# Switching_Circuits.net
KiCad netlist of a schematic drawn in Altium Designer
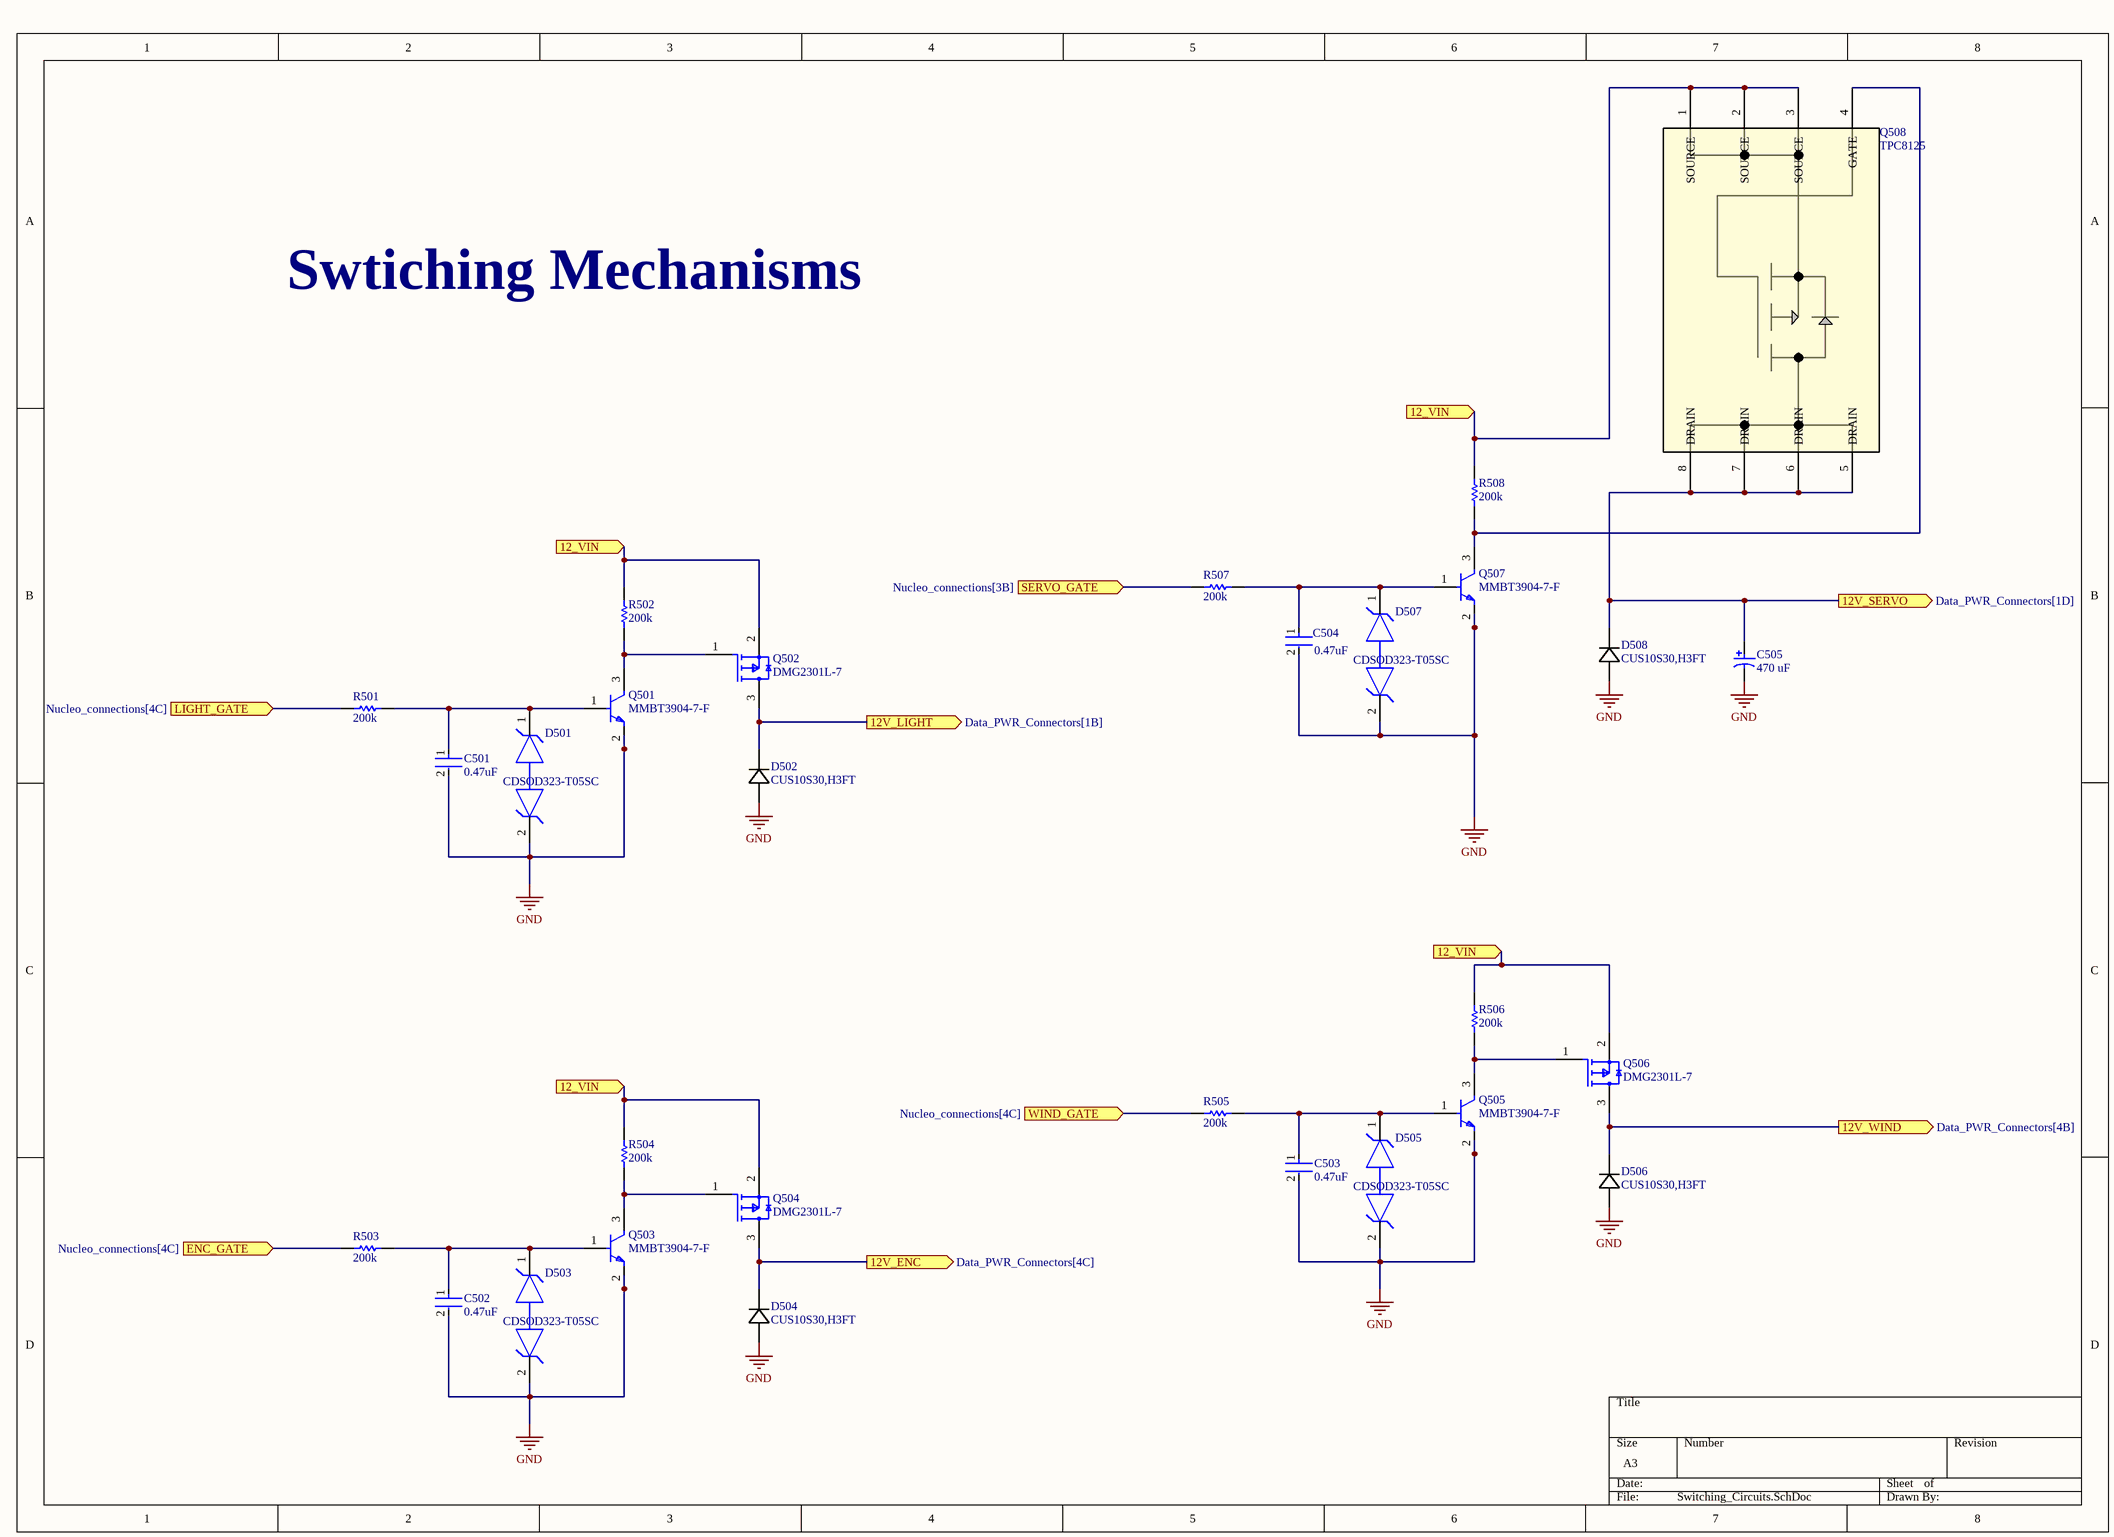
[diagram p0: Switching_Circuits.SchDoc]

(export (version "E")
  (design (tool "Eeschema 10.0.6"))
  (components
    (comp (ref "C501")
      (value "0.47uF")
      (footprint "FP-GRM21B-0_15-IPC_B")
      (description "Chip Multilayer Ceramic Capacitors for General Purpose, 0805, 0.47uF, X7R, 15%, 10%, 100V")
      (fields (field (name "VOLTAGE") "100V") (field (name "TOLERANCE") "10%"))
      (libsource (lib "Altium Content Vault") (part "b4654b650e69147ec39a6b967a45e02"))
    )
    (comp (ref "C502")
      (value "0.47uF")
      (footprint "FP-GRM21B-0_15-IPC_B")
      (description "Chip Multilayer Ceramic Capacitors for General Purpose, 0805, 0.47uF, X7R, 15%, 10%, 100V")
      (fields (field (name "VOLTAGE") "100V") (field (name "TOLERANCE") "10%"))
      (libsource (lib "Altium Content Vault") (part "b4654b650e69147ec39a6b967a45e02"))
    )
    (comp (ref "C503")
      (value "0.47uF")
      (footprint "FP-GRM21B-0_15-IPC_B")
      (description "Chip Multilayer Ceramic Capacitors for General Purpose, 0805, 0.47uF, X7R, 15%, 10%, 100V")
      (fields (field (name "VOLTAGE") "100V") (field (name "TOLERANCE") "10%"))
      (libsource (lib "Altium Content Vault") (part "b4654b650e69147ec39a6b967a45e02"))
    )
    (comp (ref "C504")
      (value "0.47uF")
      (footprint "FP-GRM21B-0_15-IPC_B")
      (description "Chip Multilayer Ceramic Capacitors for General Purpose, 0805, 0.47uF, X7R, 15%, 10%, 100V")
      (fields (field (name "VOLTAGE") "100V") (field (name "TOLERANCE") "10%"))
      (libsource (lib "Altium Content Vault") (part "b4654b650e69147ec39a6b967a45e02"))
    )
    (comp (ref "C505")
      (value "470 uF")
      (footprint "PNSC-CAP-10x20-P2")
      (description "Aluminum Electrolytic Capacitor, 470 uF, +/- 20%, 50 V, -55 to 105 degC, 2-Pin THD, RoHS, Bulk")
      (fields (field (name "MANUFACTURER") "Panasonic"))
      (libsource (lib "Altium Content Vault") (part "CAP-P-2"))
    )
    (comp (ref "D501")
      (value "CDSOD323-T05SC")
      (footprint "FP-SOD-323-CA-MFG")
      (description "TVS DIODE 5VWM 14.5VC SOD323")
      (libsource (lib "Altium Content Vault") (part "c43c1b0add0eb72e36bdc657e82fc73"))
    )
    (comp (ref "D502")
      (value "CUS10S30,H3FT")
      (footprint "USC_TOS")
      (description "No Description Available")
      (libsource (lib "Schlib1") (part "CUS10S30,H3FT"))
    )
    (comp (ref "D503")
      (value "CDSOD323-T05SC")
      (footprint "FP-SOD-323-CA-MFG")
      (description "TVS DIODE 5VWM 14.5VC SOD323")
      (libsource (lib "Altium Content Vault") (part "c43c1b0add0eb72e36bdc657e82fc73"))
    )
    (comp (ref "D504")
      (value "CUS10S30,H3FT")
      (footprint "USC_TOS")
      (description "No Description Available")
      (libsource (lib "Schlib1") (part "CUS10S30,H3FT"))
    )
    (comp (ref "D505")
      (value "CDSOD323-T05SC")
      (footprint "FP-SOD-323-CA-MFG")
      (description "TVS DIODE 5VWM 14.5VC SOD323")
      (libsource (lib "Altium Content Vault") (part "c43c1b0add0eb72e36bdc657e82fc73"))
    )
    (comp (ref "D506")
      (value "CUS10S30,H3FT")
      (footprint "USC_TOS")
      (description "No Description Available")
      (libsource (lib "Schlib1") (part "CUS10S30,H3FT"))
    )
    (comp (ref "D507")
      (value "CDSOD323-T05SC")
      (footprint "FP-SOD-323-CA-MFG")
      (description "TVS DIODE 5VWM 14.5VC SOD323")
      (libsource (lib "Altium Content Vault") (part "c43c1b0add0eb72e36bdc657e82fc73"))
    )
    (comp (ref "D508")
      (value "CUS10S30,H3FT")
      (footprint "USC_TOS")
      (description "No Description Available")
      (libsource (lib "Schlib1") (part "CUS10S30,H3FT"))
    )
    (comp (ref "Q501")
      (value "MMBT3904-7-F")
      (footprint "FP-SOT23-IPC_A")
      (description "TRANS NPN 40V 0.2A SMD SOT23-3")
      (libsource (lib "Altium Content Vault") (part "b44e953556f554d0102664c7d152cb4"))
    )
    (comp (ref "Q502")
      (value "DMG2301L-7")
      (footprint "FP-SOT23-MFG")
      (description "MOSFET P-CH 20V 3A SOT23")
      (fields
        (field (name "MANUFACTURER") "Diodes Inc.")
        (field (name "OCTOPART") "https://octopart.com/dmg2301l-7-diodes+inc.-67250456")
      )
      (libsource (lib "Altium Content Vault") (part "b8f99f9e586195791e7fb11725ebaeb"))
    )
    (comp (ref "Q503")
      (value "MMBT3904-7-F")
      (footprint "FP-SOT23-IPC_A")
      (description "TRANS NPN 40V 0.2A SMD SOT23-3")
      (libsource (lib "Altium Content Vault") (part "b44e953556f554d0102664c7d152cb4"))
    )
    (comp (ref "Q504")
      (value "DMG2301L-7")
      (footprint "FP-SOT23-MFG")
      (description "MOSFET P-CH 20V 3A SOT23")
      (fields
        (field (name "MANUFACTURER") "Diodes Inc.")
        (field (name "OCTOPART") "https://octopart.com/dmg2301l-7-diodes+inc.-67250456")
      )
      (libsource (lib "Altium Content Vault") (part "b8f99f9e586195791e7fb11725ebaeb"))
    )
    (comp (ref "Q505")
      (value "MMBT3904-7-F")
      (footprint "FP-SOT23-IPC_A")
      (description "TRANS NPN 40V 0.2A SMD SOT23-3")
      (libsource (lib "Altium Content Vault") (part "b44e953556f554d0102664c7d152cb4"))
    )
    (comp (ref "Q506")
      (value "DMG2301L-7")
      (footprint "FP-SOT23-MFG")
      (description "MOSFET P-CH 20V 3A SOT23")
      (fields
        (field (name "MANUFACTURER") "Diodes Inc.")
        (field (name "OCTOPART") "https://octopart.com/dmg2301l-7-diodes+inc.-67250456")
      )
      (libsource (lib "Altium Content Vault") (part "b8f99f9e586195791e7fb11725ebaeb"))
    )
    (comp (ref "Q507")
      (value "MMBT3904-7-F")
      (footprint "FP-SOT23-IPC_A")
      (description "TRANS NPN 40V 0.2A SMD SOT23-3")
      (libsource (lib "Altium Content Vault") (part "b44e953556f554d0102664c7d152cb4"))
    )
    (comp (ref "Q508")
      (value "TPC8125")
      (footprint "SOP-8_TOS")
      (description "No Description Available")
      (libsource (lib "Schlib1") (part "TPC8125"))
    )
    (comp (ref "R501")
      (value "200k")
      (footprint "RESC2013X70X40LL20T20")
      (fields (field (name "MANUFACTURER") "Panasonic") (field (name "PART NUMBER") "ERJ-6ENF2003V"))
      (libsource (lib "Altium Content Vault") (part "RES"))
    )
    (comp (ref "R502")
      (value "200k")
      (footprint "RESC2013X70X40LL20T20")
      (fields (field (name "MANUFACTURER") "Panasonic") (field (name "PART NUMBER") "ERJ-6ENF2003V"))
      (libsource (lib "Altium Content Vault") (part "RES"))
    )
    (comp (ref "R503")
      (value "200k")
      (footprint "RESC2013X70X40LL20T20")
      (fields (field (name "MANUFACTURER") "Panasonic") (field (name "PART NUMBER") "ERJ-6ENF2003V"))
      (libsource (lib "Altium Content Vault") (part "RES"))
    )
    (comp (ref "R504")
      (value "200k")
      (footprint "RESC2013X70X40LL20T20")
      (fields (field (name "MANUFACTURER") "Panasonic") (field (name "PART NUMBER") "ERJ-6ENF2003V"))
      (libsource (lib "Altium Content Vault") (part "RES"))
    )
    (comp (ref "R505")
      (value "200k")
      (footprint "RESC2013X70X40LL20T20")
      (fields (field (name "MANUFACTURER") "Panasonic") (field (name "PART NUMBER") "ERJ-6ENF2003V"))
      (libsource (lib "Altium Content Vault") (part "RES"))
    )
    (comp (ref "R506")
      (value "200k")
      (footprint "RESC2013X70X40LL20T20")
      (fields (field (name "MANUFACTURER") "Panasonic") (field (name "PART NUMBER") "ERJ-6ENF2003V"))
      (libsource (lib "Altium Content Vault") (part "RES"))
    )
    (comp (ref "R507")
      (value "200k")
      (footprint "RESC2013X70X40LL20T20")
      (fields (field (name "MANUFACTURER") "Panasonic") (field (name "PART NUMBER") "ERJ-6ENF2003V"))
      (libsource (lib "Altium Content Vault") (part "RES"))
    )
    (comp (ref "R508")
      (value "200k")
      (footprint "RESC2013X70X40LL20T20")
      (fields (field (name "MANUFACTURER") "Panasonic") (field (name "PART NUMBER") "ERJ-6ENF2003V"))
      (libsource (lib "Altium Content Vault") (part "RES"))
    )
  )
  (nets
    (net (code "1") (name "/12V_ENC") (class "Default")
      (node (ref "D504") (pin "1") (pinfunction "cathode_1") (pintype "passive"))
      (node (ref "Q504") (pin "3") (pinfunction "D_3") (pintype "passive"))
    )
    (net (code "2") (name "/12V_LIGHT") (class "Default")
      (node (ref "D502") (pin "1") (pinfunction "cathode_1") (pintype "passive"))
      (node (ref "Q502") (pin "3") (pinfunction "D_3") (pintype "passive"))
    )
    (net (code "3") (name "/12V_SERVO") (class "Default")
      (node (ref "C505") (pin "1") (pinfunction "1_1") (pintype "passive"))
      (node (ref "D508") (pin "1") (pinfunction "cathode_1") (pintype "passive"))
      (node (ref "Q508") (pin "5") (pinfunction "DRAIN_5") (pintype "passive"))
      (node (ref "Q508") (pin "6") (pinfunction "DRAIN_6") (pintype "passive"))
      (node (ref "Q508") (pin "7") (pinfunction "DRAIN_7") (pintype "passive"))
      (node (ref "Q508") (pin "8") (pinfunction "DRAIN_8") (pintype "passive"))
    )
    (net (code "4") (name "/12V_WIND") (class "Default")
      (node (ref "D506") (pin "1") (pinfunction "cathode_1") (pintype "passive"))
      (node (ref "Q506") (pin "3") (pinfunction "D_3") (pintype "passive"))
    )
    (net (code "5") (name "/12_VIN") (class "Default")
      (node (ref "Q502") (pin "2") (pinfunction "S_2") (pintype "passive"))
      (node (ref "Q504") (pin "2") (pinfunction "S_2") (pintype "passive"))
      (node (ref "Q506") (pin "2") (pinfunction "S_2") (pintype "passive"))
      (node (ref "Q508") (pin "1") (pinfunction "SOURCE_1") (pintype "passive"))
      (node (ref "Q508") (pin "2") (pinfunction "SOURCE_2") (pintype "passive"))
      (node (ref "Q508") (pin "3") (pinfunction "SOURCE_3") (pintype "passive"))
      (node (ref "R502") (pin "2") (pinfunction "2_2") (pintype "passive"))
      (node (ref "R504") (pin "2") (pinfunction "2_2") (pintype "passive"))
      (node (ref "R506") (pin "2") (pinfunction "2_2") (pintype "passive"))
      (node (ref "R508") (pin "2") (pinfunction "2_2") (pintype "passive"))
    )
    (net (code "6") (name "/ENC_GATE") (class "Default")
      (node (ref "R503") (pin "1") (pinfunction "1_1") (pintype "passive"))
    )
    (net (code "7") (name "/LIGHT_GATE") (class "Default")
      (node (ref "R501") (pin "1") (pinfunction "1_1") (pintype "passive"))
    )
    (net (code "8") (name "/SERVO_GATE") (class "Default")
      (node (ref "R507") (pin "1") (pinfunction "1_1") (pintype "passive"))
    )
    (net (code "9") (name "/WIND_GATE") (class "Default")
      (node (ref "R505") (pin "1") (pinfunction "1_1") (pintype "passive"))
    )
    (net (code "10") (name "GND") (class "Default")
      (node (ref "C501") (pin "2") (pinfunction "2_2") (pintype "passive"))
      (node (ref "C502") (pin "2") (pinfunction "2_2") (pintype "passive"))
      (node (ref "C503") (pin "2") (pinfunction "2_2") (pintype "passive"))
      (node (ref "C504") (pin "2") (pinfunction "2_2") (pintype "passive"))
      (node (ref "C505") (pin "2") (pinfunction "2_2") (pintype "passive"))
      (node (ref "D501") (pin "2") (pinfunction "2_2") (pintype "passive"))
      (node (ref "D502") (pin "2") (pinfunction "anode_2") (pintype "passive"))
      (node (ref "D503") (pin "2") (pinfunction "2_2") (pintype "passive"))
      (node (ref "D504") (pin "2") (pinfunction "anode_2") (pintype "passive"))
      (node (ref "D505") (pin "2") (pinfunction "2_2") (pintype "passive"))
      (node (ref "D506") (pin "2") (pinfunction "anode_2") (pintype "passive"))
      (node (ref "D507") (pin "2") (pinfunction "2_2") (pintype "passive"))
      (node (ref "D508") (pin "2") (pinfunction "anode_2") (pintype "passive"))
      (node (ref "Q501") (pin "2") (pinfunction "E_2") (pintype "passive"))
      (node (ref "Q503") (pin "2") (pinfunction "E_2") (pintype "passive"))
      (node (ref "Q505") (pin "2") (pinfunction "E_2") (pintype "passive"))
      (node (ref "Q507") (pin "2") (pinfunction "E_2") (pintype "passive"))
    )
    (net (code "11") (name "Net-(Q501-B)") (class "Default")
      (node (ref "C501") (pin "1") (pinfunction "1_1") (pintype "passive"))
      (node (ref "D501") (pin "1") (pinfunction "1_1") (pintype "passive"))
      (node (ref "Q501") (pin "1") (pinfunction "B_1") (pintype "passive"))
      (node (ref "R501") (pin "2") (pinfunction "2_2") (pintype "passive"))
    )
    (net (code "12") (name "Net-(Q501-C)") (class "Default")
      (node (ref "Q501") (pin "3") (pinfunction "C_3") (pintype "passive"))
      (node (ref "Q502") (pin "1") (pinfunction "G_1") (pintype "passive"))
      (node (ref "R502") (pin "1") (pinfunction "1_1") (pintype "passive"))
    )
    (net (code "13") (name "Net-(Q503-B)") (class "Default")
      (node (ref "C502") (pin "1") (pinfunction "1_1") (pintype "passive"))
      (node (ref "D503") (pin "1") (pinfunction "1_1") (pintype "passive"))
      (node (ref "Q503") (pin "1") (pinfunction "B_1") (pintype "passive"))
      (node (ref "R503") (pin "2") (pinfunction "2_2") (pintype "passive"))
    )
    (net (code "14") (name "Net-(Q503-C)") (class "Default")
      (node (ref "Q503") (pin "3") (pinfunction "C_3") (pintype "passive"))
      (node (ref "Q504") (pin "1") (pinfunction "G_1") (pintype "passive"))
      (node (ref "R504") (pin "1") (pinfunction "1_1") (pintype "passive"))
    )
    (net (code "15") (name "Net-(Q505-B)") (class "Default")
      (node (ref "C503") (pin "1") (pinfunction "1_1") (pintype "passive"))
      (node (ref "D505") (pin "1") (pinfunction "1_1") (pintype "passive"))
      (node (ref "Q505") (pin "1") (pinfunction "B_1") (pintype "passive"))
      (node (ref "R505") (pin "2") (pinfunction "2_2") (pintype "passive"))
    )
    (net (code "16") (name "Net-(Q505-C)") (class "Default")
      (node (ref "Q505") (pin "3") (pinfunction "C_3") (pintype "passive"))
      (node (ref "Q506") (pin "1") (pinfunction "G_1") (pintype "passive"))
      (node (ref "R506") (pin "1") (pinfunction "1_1") (pintype "passive"))
    )
    (net (code "17") (name "Net-(Q507-B)") (class "Default")
      (node (ref "C504") (pin "1") (pinfunction "1_1") (pintype "passive"))
      (node (ref "D507") (pin "1") (pinfunction "1_1") (pintype "passive"))
      (node (ref "Q507") (pin "1") (pinfunction "B_1") (pintype "passive"))
      (node (ref "R507") (pin "2") (pinfunction "2_2") (pintype "passive"))
    )
    (net (code "18") (name "Net-(Q507-C)") (class "Default")
      (node (ref "Q507") (pin "3") (pinfunction "C_3") (pintype "passive"))
      (node (ref "Q508") (pin "4") (pinfunction "GATE_4") (pintype "passive"))
      (node (ref "R508") (pin "1") (pinfunction "1_1") (pintype "passive"))
    )
  )
)
